# esquematico_RLEG_groundplane_v3.net
KiCad netlist of a schematic drawn in EAGLE
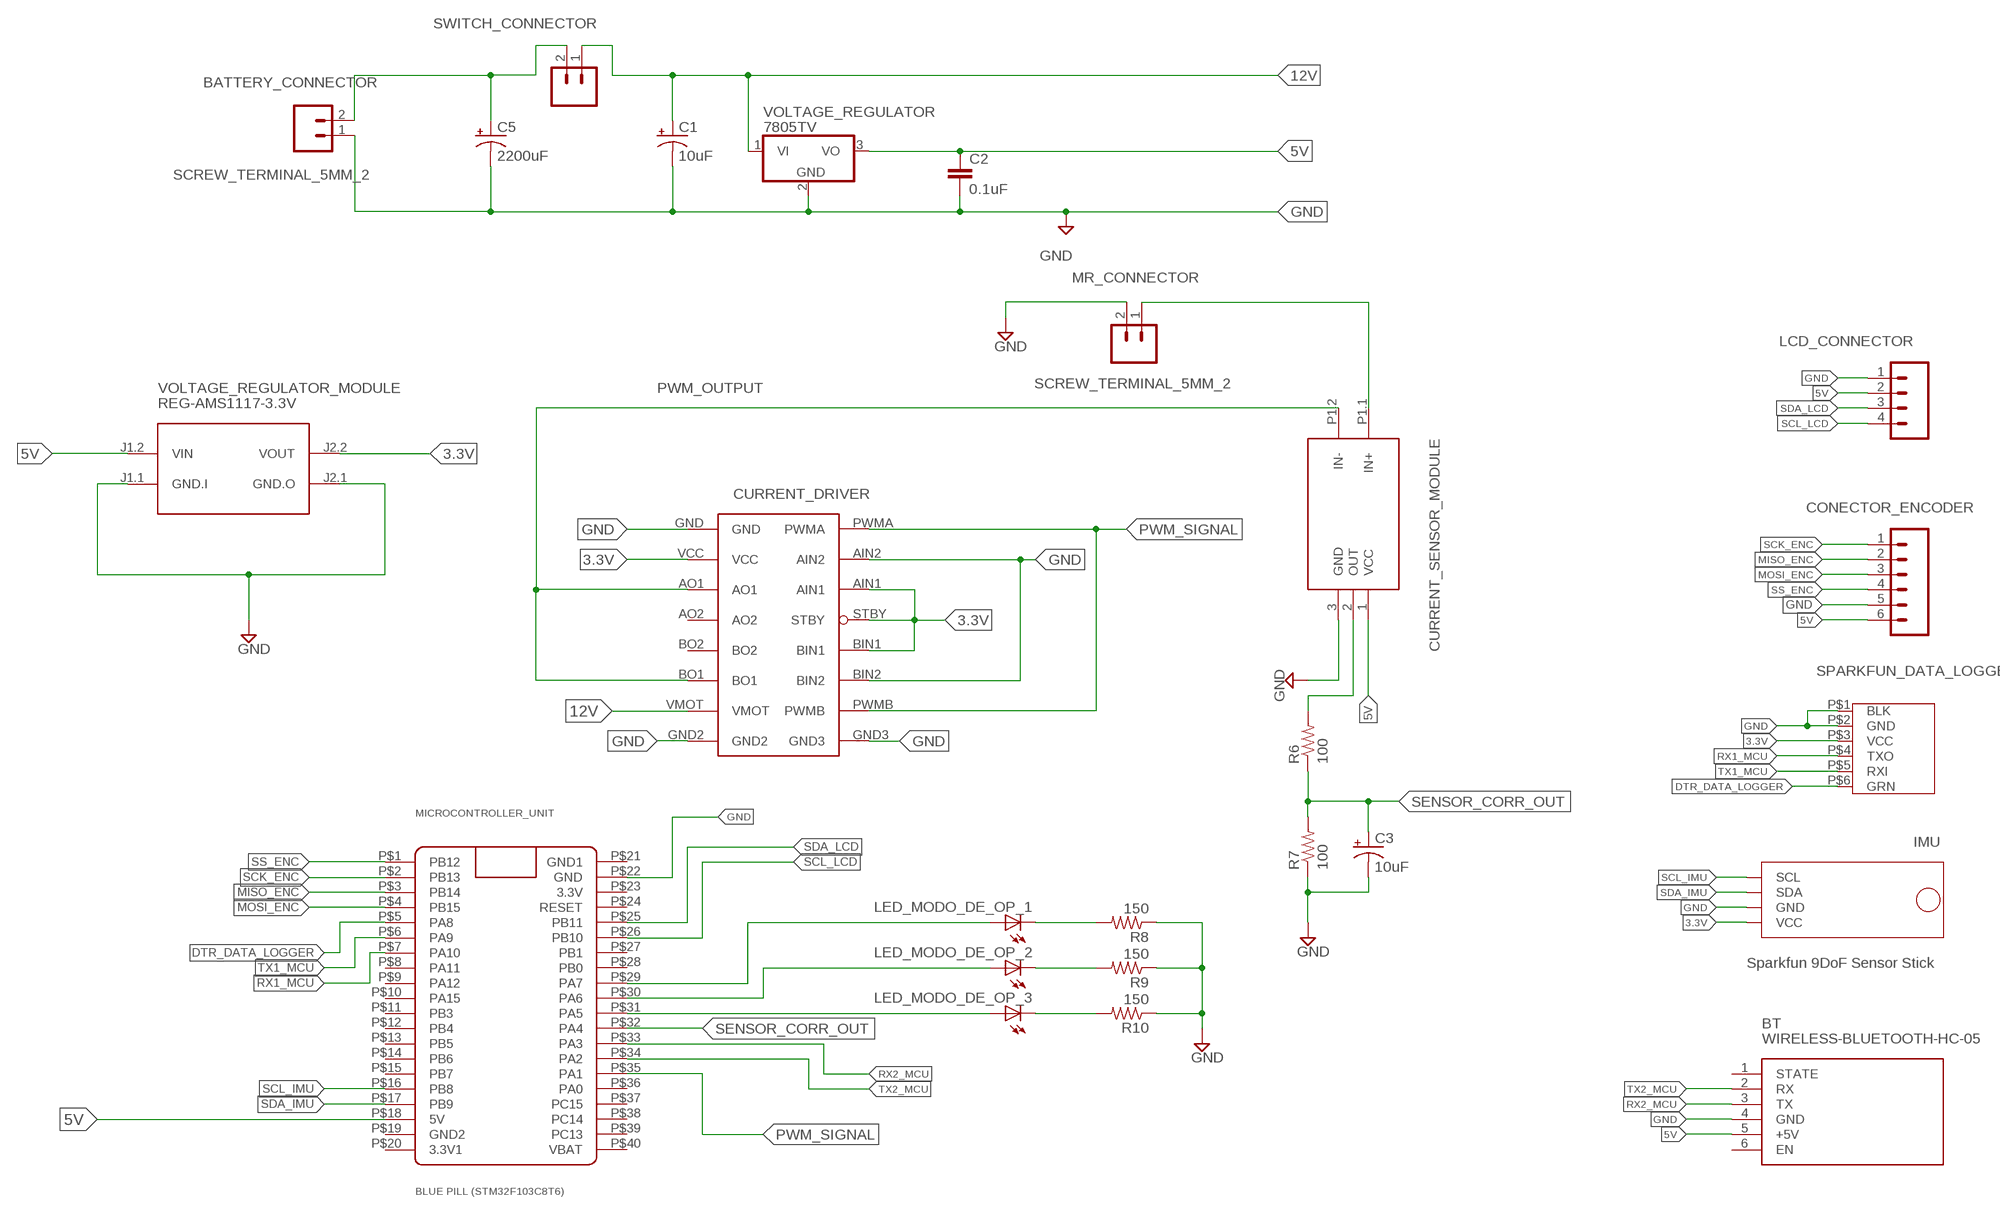
[diagram p0: schematic, sheet 1]

(export (version "E")
  (design (tool "Eeschema 10.0.6"))
  (components
    (comp (ref "BATTERY_CONNECTOR")
      (value "SCREW_TERMINAL_5MM_2")
      (footprint "eagle-import:SCREWTERMINAL-5MM-2")
      (libsource (lib "eagle-import") (part "CONN_025MM"))
    )
    (comp (ref "BT")
      (value "WIRELESS-BLUETOOTH-HC-05")
      (footprint "eagle-import:WIRELESS-BLUETOOTH-HC-05")
      (libsource (lib "eagle-import") (part "WIRELESS-BLUETOOTH-HC-05"))
    )
    (comp (ref "C1")
      (value "10uF")
      (footprint "eagle-import:E5-5")
      (libsource (lib "eagle-import") (part "CPOL-USE5-5"))
    )
    (comp (ref "C2")
      (value "0.1uF")
      (footprint "eagle-import:C2.5-4")
      (libsource (lib "eagle-import") (part "C2.5/4"))
    )
    (comp (ref "C3")
      (value "10uF")
      (footprint "eagle-import:E5-5")
      (libsource (lib "eagle-import") (part "CPOL-USE5-5"))
    )
    (comp (ref "C5")
      (value "2200uF")
      (footprint "eagle-import:E5-13")
      (libsource (lib "eagle-import") (part "CPOL-USE5-13"))
    )
    (comp (ref "CONECTOR_ENCODER")
      (value "a")
      (footprint "eagle-import:MOLEX-1X6")
      (libsource (lib "eagle-import") (part "CONN_06POLAR"))
    )
    (comp (ref "CURRENT_DRIVER")
      (value "TB6612FNG")
      (footprint "eagle-import:TB6612FNG")
      (libsource (lib "eagle-import") (part "TB6612FNG"))
    )
    (comp (ref "CURRENT_SENSOR_MODULE")
      (value "CURRENT-SENSOR-ACS712#IC")
      (footprint "eagle-import:CURRENT-SENSOR-ACS712#IC")
      (libsource (lib "eagle-import") (part "CURRENT-SENSOR-ACS712#IC"))
    )
    (comp (ref "IMU")
      (value "Sparkfun 9DoF Sensor Stick")
      (footprint "eagle-import:IMU")
      (libsource (lib "eagle-import") (part "IMU"))
    )
    (comp (ref "LCD_CONNECTOR")
      (value "CONN_04POLAR")
      (footprint "eagle-import:MOLEX-1X4")
      (libsource (lib "eagle-import") (part "CONN_04POLAR"))
    )
    (comp (ref "LED_MODO_DE_OP_1")
      (value "LED3MM")
      (footprint "eagle-import:LED3MM")
      (libsource (lib "eagle-import") (part "LED3MM"))
    )
    (comp (ref "LED_MODO_DE_OP_2")
      (value "LED3MM")
      (footprint "eagle-import:LED3MM")
      (libsource (lib "eagle-import") (part "LED3MM"))
    )
    (comp (ref "LED_MODO_DE_OP_3")
      (value "LED3MM")
      (footprint "eagle-import:LED3MM")
      (libsource (lib "eagle-import") (part "LED3MM"))
    )
    (comp (ref "MICROCONTROLLER_UNIT")
      (value "BLUE PILL (STM32F103C8T6)")
      (footprint "eagle-import:BLUE_PILL")
      (libsource (lib "eagle-import") (part "BLUE_PILL"))
    )
    (comp (ref "MR_CONNECTOR")
      (value "SCREW_TERMINAL_5MM_2")
      (footprint "eagle-import:SCREWTERMINAL-5MM-2")
      (libsource (lib "eagle-import") (part "CONN_025MM"))
    )
    (comp (ref "R6")
      (value "100")
      (footprint "eagle-import:0207_9")
      (libsource (lib "eagle-import") (part "R-US_0207/9"))
    )
    (comp (ref "R7")
      (value "100")
      (footprint "eagle-import:0207_9")
      (libsource (lib "eagle-import") (part "R-US_0207/9"))
    )
    (comp (ref "R8")
      (value "150")
      (footprint "eagle-import:0207_9")
      (libsource (lib "eagle-import") (part "R-US_0207/9"))
    )
    (comp (ref "R9")
      (value "150")
      (footprint "eagle-import:0207_9")
      (libsource (lib "eagle-import") (part "R-US_0207/9"))
    )
    (comp (ref "R10")
      (value "150")
      (footprint "eagle-import:0207_9")
      (libsource (lib "eagle-import") (part "R-US_0207/9"))
    )
    (comp (ref "SPARKFUN_DATA_LOGGER")
      (value "DATA_LOGGER")
      (footprint "eagle-import:DATA_LOGGER")
      (libsource (lib "eagle-import") (part "DATA_LOGGER"))
    )
    (comp (ref "SWITCH_CONNECTOR")
      (value "CONN_02POLAR")
      (footprint "eagle-import:MOLEX-1X2")
      (libsource (lib "eagle-import") (part "CONN_02POLAR"))
    )
    (comp (ref "VOLTAGE_REGULATOR")
      (value "7805TV")
      (footprint "eagle-import:TO220V")
      (libsource (lib "eagle-import") (part "78TV05"))
    )
    (comp (ref "VOLTAGE_REGULATOR_MODULE")
      (value "REG-AMS1117-3.3V")
      (footprint "eagle-import:REG-AMS1117")
      (libsource (lib "eagle-import") (part "REG-AMS1117-3.3V"))
    )
  )
  (nets
    (net (code "1") (name "/GND1") (class "Default")
      (node (ref "MICROCONTROLLER_UNIT") (pin "P$21") (pinfunction "GND1_P$21") (pintype "power_in"))
    )
    (net (code "2") (name "/PWM_OUTPUT") (class "Default")
      (node (ref "CURRENT_DRIVER") (pin "AO1") (pinfunction "AO1_AO1") (pintype "bidirectional"))
      (node (ref "CURRENT_DRIVER") (pin "BO1") (pinfunction "BO1_BO1") (pintype "bidirectional"))
      (node (ref "CURRENT_SENSOR_MODULE") (pin "P1.2") (pinfunction "IN-_P1.2") (pintype "bidirectional"))
    )
    (net (code "3") (name "3.3V") (class "Default")
      (node (ref "CURRENT_DRIVER") (pin "AIN1") (pinfunction "AIN1_AIN1") (pintype "bidirectional"))
      (node (ref "CURRENT_DRIVER") (pin "BIN1") (pinfunction "BIN1_BIN1") (pintype "bidirectional"))
      (node (ref "CURRENT_DRIVER") (pin "STBY") (pinfunction "STBY_STBY") (pintype "bidirectional"))
      (node (ref "CURRENT_DRIVER") (pin "VCC") (pinfunction "VCC_VCC") (pintype "bidirectional"))
      (node (ref "IMU") (pin "VCC") (pinfunction "VCC_VCC") (pintype "bidirectional"))
      (node (ref "SPARKFUN_DATA_LOGGER") (pin "P$3") (pinfunction "VCC_P$3") (pintype "power_in"))
      (node (ref "VOLTAGE_REGULATOR_MODULE") (pin "J2.2") (pinfunction "VOUT_J2.2") (pintype "bidirectional"))
    )
    (net (code "4") (name "5V") (class "Default")
      (node (ref "BT") (pin "5") (pinfunction "+5V_5") (pintype "power_in"))
      (node (ref "C2") (pin "1") (pinfunction "1_1") (pintype "passive"))
      (node (ref "CONECTOR_ENCODER") (pin "6") (pinfunction "6_6") (pintype "passive"))
      (node (ref "CURRENT_SENSOR_MODULE") (pin "1") (pinfunction "VCC_1") (pintype "power_in"))
      (node (ref "LCD_CONNECTOR") (pin "2") (pinfunction "2_2") (pintype "passive"))
      (node (ref "MICROCONTROLLER_UNIT") (pin "P$18") (pinfunction "5V_P$18") (pintype "bidirectional"))
      (node (ref "VOLTAGE_REGULATOR") (pin "3") (pinfunction "VO_3") (pintype "passive"))
      (node (ref "VOLTAGE_REGULATOR_MODULE") (pin "J1.2") (pinfunction "VIN_J1.2") (pintype "bidirectional"))
    )
    (net (code "5") (name "12V") (class "Default")
      (node (ref "C1") (pin "+") (pinfunction "+_+") (pintype "passive"))
      (node (ref "CURRENT_DRIVER") (pin "VMOT") (pinfunction "VMOT_VMOT") (pintype "bidirectional"))
      (node (ref "SWITCH_CONNECTOR") (pin "1") (pinfunction "1_1") (pintype "passive"))
      (node (ref "VOLTAGE_REGULATOR") (pin "1") (pinfunction "VI_1") (pintype "input"))
    )
    (net (code "6") (name "DTR_DATA_LOGGER") (class "Default")
      (node (ref "MICROCONTROLLER_UNIT") (pin "P$5") (pinfunction "PA8_P$5") (pintype "bidirectional"))
      (node (ref "SPARKFUN_DATA_LOGGER") (pin "P$6") (pinfunction "GRN_P$6") (pintype "input"))
    )
    (net (code "7") (name "GND") (class "Default")
      (node (ref "BATTERY_CONNECTOR") (pin "1") (pinfunction "1_1") (pintype "passive"))
      (node (ref "BT") (pin "4") (pinfunction "GND_4") (pintype "power_in"))
      (node (ref "C1") (pin "-") (pinfunction "-_-") (pintype "passive"))
      (node (ref "C2") (pin "2") (pinfunction "2_2") (pintype "passive"))
      (node (ref "C3") (pin "-") (pinfunction "-_-") (pintype "passive"))
      (node (ref "C5") (pin "-") (pinfunction "-_-") (pintype "passive"))
      (node (ref "CONECTOR_ENCODER") (pin "5") (pinfunction "5_5") (pintype "passive"))
      (node (ref "CURRENT_DRIVER") (pin "AIN2") (pinfunction "AIN2_AIN2") (pintype "bidirectional"))
      (node (ref "CURRENT_DRIVER") (pin "BIN2") (pinfunction "BIN2_BIN2") (pintype "bidirectional"))
      (node (ref "CURRENT_DRIVER") (pin "GND") (pinfunction "GND_GND") (pintype "bidirectional"))
      (node (ref "CURRENT_DRIVER") (pin "GND2") (pinfunction "GND2_GND2") (pintype "bidirectional"))
      (node (ref "CURRENT_DRIVER") (pin "GND3") (pinfunction "GND3_GND3") (pintype "bidirectional"))
      (node (ref "CURRENT_SENSOR_MODULE") (pin "3") (pinfunction "GND_3") (pintype "power_in"))
      (node (ref "IMU") (pin "GND") (pinfunction "GND_GND") (pintype "bidirectional"))
      (node (ref "LCD_CONNECTOR") (pin "1") (pinfunction "1_1") (pintype "passive"))
      (node (ref "MICROCONTROLLER_UNIT") (pin "P$22") (pinfunction "GND_P$22") (pintype "bidirectional"))
      (node (ref "MR_CONNECTOR") (pin "2") (pinfunction "2_2") (pintype "passive"))
      (node (ref "R10") (pin "1") (pinfunction "1_1") (pintype "passive"))
      (node (ref "R7") (pin "1") (pinfunction "1_1") (pintype "passive"))
      (node (ref "R8") (pin "1") (pinfunction "1_1") (pintype "passive"))
      (node (ref "R9") (pin "1") (pinfunction "1_1") (pintype "passive"))
      (node (ref "SPARKFUN_DATA_LOGGER") (pin "P$1") (pinfunction "BLK_P$1") (pintype "power_in"))
      (node (ref "SPARKFUN_DATA_LOGGER") (pin "P$2") (pinfunction "GND_P$2") (pintype "power_in"))
      (node (ref "VOLTAGE_REGULATOR") (pin "2") (pinfunction "GND_2") (pintype "passive"))
      (node (ref "VOLTAGE_REGULATOR_MODULE") (pin "J1.1") (pinfunction "GND.I_J1.1") (pintype "bidirectional"))
      (node (ref "VOLTAGE_REGULATOR_MODULE") (pin "J2.1") (pinfunction "GND.O_J2.1") (pintype "bidirectional"))
    )
    (net (code "8") (name "MISO_ENC") (class "Default")
      (node (ref "CONECTOR_ENCODER") (pin "2") (pinfunction "2_2") (pintype "passive"))
      (node (ref "MICROCONTROLLER_UNIT") (pin "P$3") (pinfunction "PB14_P$3") (pintype "bidirectional"))
    )
    (net (code "9") (name "MOSI_ENC") (class "Default")
      (node (ref "CONECTOR_ENCODER") (pin "3") (pinfunction "3_3") (pintype "passive"))
      (node (ref "MICROCONTROLLER_UNIT") (pin "P$4") (pinfunction "PB15_P$4") (pintype "bidirectional"))
    )
    (net (code "10") (name "Net-(BATTERY_CONNECTOR-Pad2)") (class "Default")
      (node (ref "BATTERY_CONNECTOR") (pin "2") (pinfunction "2_2") (pintype "passive"))
      (node (ref "C5") (pin "+") (pinfunction "+_+") (pintype "passive"))
      (node (ref "SWITCH_CONNECTOR") (pin "2") (pinfunction "2_2") (pintype "passive"))
    )
    (net (code "11") (name "Net-(CURRENT_SENSOR_MODULE-IN+)") (class "Default")
      (node (ref "CURRENT_SENSOR_MODULE") (pin "P1.1") (pinfunction "IN+_P1.1") (pintype "bidirectional"))
      (node (ref "MR_CONNECTOR") (pin "1") (pinfunction "1_1") (pintype "passive"))
    )
    (net (code "12") (name "Net-(CURRENT_SENSOR_MODULE-OUT)") (class "Default")
      (node (ref "CURRENT_SENSOR_MODULE") (pin "2") (pinfunction "OUT_2") (pintype "output"))
      (node (ref "R6") (pin "2") (pinfunction "2_2") (pintype "passive"))
    )
    (net (code "13") (name "Net-(LED_MODO_DE_OP_1-C)") (class "Default")
      (node (ref "LED_MODO_DE_OP_1") (pin "K") (pinfunction "C_K") (pintype "passive"))
      (node (ref "R8") (pin "2") (pinfunction "2_2") (pintype "passive"))
    )
    (net (code "14") (name "Net-(LED_MODO_DE_OP_2-C)") (class "Default")
      (node (ref "LED_MODO_DE_OP_2") (pin "K") (pinfunction "C_K") (pintype "passive"))
      (node (ref "R9") (pin "2") (pinfunction "2_2") (pintype "passive"))
    )
    (net (code "15") (name "Net-(LED_MODO_DE_OP_3-C)") (class "Default")
      (node (ref "LED_MODO_DE_OP_3") (pin "K") (pinfunction "C_K") (pintype "passive"))
      (node (ref "R10") (pin "2") (pinfunction "2_2") (pintype "passive"))
    )
    (net (code "16") (name "Net-(MICROCONTROLLER_UNIT-PA5)") (class "Default")
      (node (ref "LED_MODO_DE_OP_3") (pin "A") (pinfunction "A_A") (pintype "passive"))
      (node (ref "MICROCONTROLLER_UNIT") (pin "P$31") (pinfunction "PA5_P$31") (pintype "bidirectional"))
    )
    (net (code "17") (name "Net-(MICROCONTROLLER_UNIT-PA6)") (class "Default")
      (node (ref "LED_MODO_DE_OP_2") (pin "A") (pinfunction "A_A") (pintype "passive"))
      (node (ref "MICROCONTROLLER_UNIT") (pin "P$30") (pinfunction "PA6_P$30") (pintype "bidirectional"))
    )
    (net (code "18") (name "Net-(MICROCONTROLLER_UNIT-PA7)") (class "Default")
      (node (ref "LED_MODO_DE_OP_1") (pin "A") (pinfunction "A_A") (pintype "passive"))
      (node (ref "MICROCONTROLLER_UNIT") (pin "P$29") (pinfunction "PA7_P$29") (pintype "bidirectional"))
    )
    (net (code "19") (name "PWM_SIGNAL") (class "Default")
      (node (ref "CURRENT_DRIVER") (pin "PWMA") (pinfunction "PWMA_PWMA") (pintype "bidirectional"))
      (node (ref "CURRENT_DRIVER") (pin "PWMB") (pinfunction "PWMB_PWMB") (pintype "bidirectional"))
      (node (ref "MICROCONTROLLER_UNIT") (pin "P$35") (pinfunction "PA1_P$35") (pintype "bidirectional"))
    )
    (net (code "20") (name "RX1_MCU") (class "Default")
      (node (ref "MICROCONTROLLER_UNIT") (pin "P$7") (pinfunction "PA10_P$7") (pintype "bidirectional"))
      (node (ref "SPARKFUN_DATA_LOGGER") (pin "P$4") (pinfunction "TXO_P$4") (pintype "output"))
    )
    (net (code "21") (name "RX2_MCU") (class "Default")
      (node (ref "BT") (pin "3") (pinfunction "TX_3") (pintype "bidirectional"))
      (node (ref "MICROCONTROLLER_UNIT") (pin "P$33") (pinfunction "PA3_P$33") (pintype "bidirectional"))
    )
    (net (code "22") (name "SCK_ENC") (class "Default")
      (node (ref "CONECTOR_ENCODER") (pin "1") (pinfunction "1_1") (pintype "passive"))
      (node (ref "MICROCONTROLLER_UNIT") (pin "P$2") (pinfunction "PB13_P$2") (pintype "bidirectional"))
    )
    (net (code "23") (name "SCL_IMU") (class "Default")
      (node (ref "IMU") (pin "SCL") (pinfunction "SCL_SCL") (pintype "bidirectional"))
      (node (ref "MICROCONTROLLER_UNIT") (pin "P$16") (pinfunction "PB8_P$16") (pintype "bidirectional"))
    )
    (net (code "24") (name "SCL_LCD") (class "Default")
      (node (ref "LCD_CONNECTOR") (pin "4") (pinfunction "4_4") (pintype "passive"))
      (node (ref "MICROCONTROLLER_UNIT") (pin "P$26") (pinfunction "PB10_P$26") (pintype "bidirectional"))
    )
    (net (code "25") (name "SDA_IMU") (class "Default")
      (node (ref "IMU") (pin "SDA") (pinfunction "SDA_SDA") (pintype "bidirectional"))
      (node (ref "MICROCONTROLLER_UNIT") (pin "P$17") (pinfunction "PB9_P$17") (pintype "bidirectional"))
    )
    (net (code "26") (name "SDA_LCD") (class "Default")
      (node (ref "LCD_CONNECTOR") (pin "3") (pinfunction "3_3") (pintype "passive"))
      (node (ref "MICROCONTROLLER_UNIT") (pin "P$25") (pinfunction "PB11_P$25") (pintype "bidirectional"))
    )
    (net (code "27") (name "SENSOR_CORR_OUT") (class "Default")
      (node (ref "C3") (pin "+") (pinfunction "+_+") (pintype "passive"))
      (node (ref "MICROCONTROLLER_UNIT") (pin "P$32") (pinfunction "PA4_P$32") (pintype "bidirectional"))
      (node (ref "R6") (pin "1") (pinfunction "1_1") (pintype "passive"))
      (node (ref "R7") (pin "2") (pinfunction "2_2") (pintype "passive"))
    )
    (net (code "28") (name "SS_ENC") (class "Default")
      (node (ref "CONECTOR_ENCODER") (pin "4") (pinfunction "4_4") (pintype "passive"))
      (node (ref "MICROCONTROLLER_UNIT") (pin "P$1") (pinfunction "PB12_P$1") (pintype "bidirectional"))
    )
    (net (code "29") (name "TX1_MCU") (class "Default")
      (node (ref "MICROCONTROLLER_UNIT") (pin "P$6") (pinfunction "PA9_P$6") (pintype "bidirectional"))
      (node (ref "SPARKFUN_DATA_LOGGER") (pin "P$5") (pinfunction "RXI_P$5") (pintype "input"))
    )
    (net (code "30") (name "TX2_MCU") (class "Default")
      (node (ref "BT") (pin "2") (pinfunction "RX_2") (pintype "bidirectional"))
      (node (ref "MICROCONTROLLER_UNIT") (pin "P$34") (pinfunction "PA2_P$34") (pintype "bidirectional"))
    )
    (net (code "31") (name "unconnected-(BT-EN-Pad6)") (class "Default")
      (node (ref "BT") (pin "6") (pinfunction "EN_6") (pintype "bidirectional"))
    )
    (net (code "32") (name "unconnected-(BT-STATE-Pad1)") (class "Default")
      (node (ref "BT") (pin "1") (pinfunction "STATE_1") (pintype "bidirectional"))
    )
    (net (code "33") (name "unconnected-(CURRENT_DRIVER-PadAO2)") (class "Default")
      (node (ref "CURRENT_DRIVER") (pin "AO2") (pinfunction "AO2_AO2") (pintype "bidirectional"))
    )
    (net (code "34") (name "unconnected-(CURRENT_DRIVER-PadBO2)") (class "Default")
      (node (ref "CURRENT_DRIVER") (pin "BO2") (pinfunction "BO2_BO2") (pintype "bidirectional"))
    )
    (net (code "35") (name "unconnected-(MICROCONTROLLER_UNIT-3.3V-PadP$23)") (class "Default")
      (node (ref "MICROCONTROLLER_UNIT") (pin "P$23") (pinfunction "3.3V_P$23") (pintype "bidirectional"))
    )
    (net (code "36") (name "unconnected-(MICROCONTROLLER_UNIT-3.3V1-PadP$20)") (class "Default")
      (node (ref "MICROCONTROLLER_UNIT") (pin "P$20") (pinfunction "3.3V1_P$20") (pintype "bidirectional"))
    )
    (net (code "37") (name "unconnected-(MICROCONTROLLER_UNIT-GND2-PadP$19)") (class "Default")
      (node (ref "MICROCONTROLLER_UNIT") (pin "P$19") (pinfunction "GND2_P$19") (pintype "bidirectional"))
    )
    (net (code "38") (name "unconnected-(MICROCONTROLLER_UNIT-PA0-PadP$36)") (class "Default")
      (node (ref "MICROCONTROLLER_UNIT") (pin "P$36") (pinfunction "PA0_P$36") (pintype "bidirectional"))
    )
    (net (code "39") (name "unconnected-(MICROCONTROLLER_UNIT-PA11-PadP$8)") (class "Default")
      (node (ref "MICROCONTROLLER_UNIT") (pin "P$8") (pinfunction "PA11_P$8") (pintype "bidirectional"))
    )
    (net (code "40") (name "unconnected-(MICROCONTROLLER_UNIT-PA12-PadP$9)") (class "Default")
      (node (ref "MICROCONTROLLER_UNIT") (pin "P$9") (pinfunction "PA12_P$9") (pintype "bidirectional"))
    )
    (net (code "41") (name "unconnected-(MICROCONTROLLER_UNIT-PA15-PadP$10)") (class "Default")
      (node (ref "MICROCONTROLLER_UNIT") (pin "P$10") (pinfunction "PA15_P$10") (pintype "bidirectional"))
    )
    (net (code "42") (name "unconnected-(MICROCONTROLLER_UNIT-PB0-PadP$28)") (class "Default")
      (node (ref "MICROCONTROLLER_UNIT") (pin "P$28") (pinfunction "PB0_P$28") (pintype "bidirectional"))
    )
    (net (code "43") (name "unconnected-(MICROCONTROLLER_UNIT-PB1-PadP$27)") (class "Default")
      (node (ref "MICROCONTROLLER_UNIT") (pin "P$27") (pinfunction "PB1_P$27") (pintype "bidirectional"))
    )
    (net (code "44") (name "unconnected-(MICROCONTROLLER_UNIT-PB3-PadP$11)") (class "Default")
      (node (ref "MICROCONTROLLER_UNIT") (pin "P$11") (pinfunction "PB3_P$11") (pintype "bidirectional"))
    )
    (net (code "45") (name "unconnected-(MICROCONTROLLER_UNIT-PB4-PadP$12)") (class "Default")
      (node (ref "MICROCONTROLLER_UNIT") (pin "P$12") (pinfunction "PB4_P$12") (pintype "bidirectional"))
    )
    (net (code "46") (name "unconnected-(MICROCONTROLLER_UNIT-PB5-PadP$13)") (class "Default")
      (node (ref "MICROCONTROLLER_UNIT") (pin "P$13") (pinfunction "PB5_P$13") (pintype "bidirectional"))
    )
    (net (code "47") (name "unconnected-(MICROCONTROLLER_UNIT-PB6-PadP$14)") (class "Default")
      (node (ref "MICROCONTROLLER_UNIT") (pin "P$14") (pinfunction "PB6_P$14") (pintype "bidirectional"))
    )
    (net (code "48") (name "unconnected-(MICROCONTROLLER_UNIT-PB7-PadP$15)") (class "Default")
      (node (ref "MICROCONTROLLER_UNIT") (pin "P$15") (pinfunction "PB7_P$15") (pintype "bidirectional"))
    )
    (net (code "49") (name "unconnected-(MICROCONTROLLER_UNIT-PC13-PadP$39)") (class "Default")
      (node (ref "MICROCONTROLLER_UNIT") (pin "P$39") (pinfunction "PC13_P$39") (pintype "bidirectional"))
    )
    (net (code "50") (name "unconnected-(MICROCONTROLLER_UNIT-PC14-PadP$38)") (class "Default")
      (node (ref "MICROCONTROLLER_UNIT") (pin "P$38") (pinfunction "PC14_P$38") (pintype "bidirectional"))
    )
    (net (code "51") (name "unconnected-(MICROCONTROLLER_UNIT-PC15-PadP$37)") (class "Default")
      (node (ref "MICROCONTROLLER_UNIT") (pin "P$37") (pinfunction "PC15_P$37") (pintype "bidirectional"))
    )
    (net (code "52") (name "unconnected-(MICROCONTROLLER_UNIT-RESET-PadP$24)") (class "Default")
      (node (ref "MICROCONTROLLER_UNIT") (pin "P$24") (pinfunction "RESET_P$24") (pintype "bidirectional"))
    )
    (net (code "53") (name "unconnected-(MICROCONTROLLER_UNIT-VBAT-PadP$40)") (class "Default")
      (node (ref "MICROCONTROLLER_UNIT") (pin "P$40") (pinfunction "VBAT_P$40") (pintype "bidirectional"))
    )
  )
)
